# midi_block_R2_2.net
KiCad netlist of a schematic drawn in EAGLE
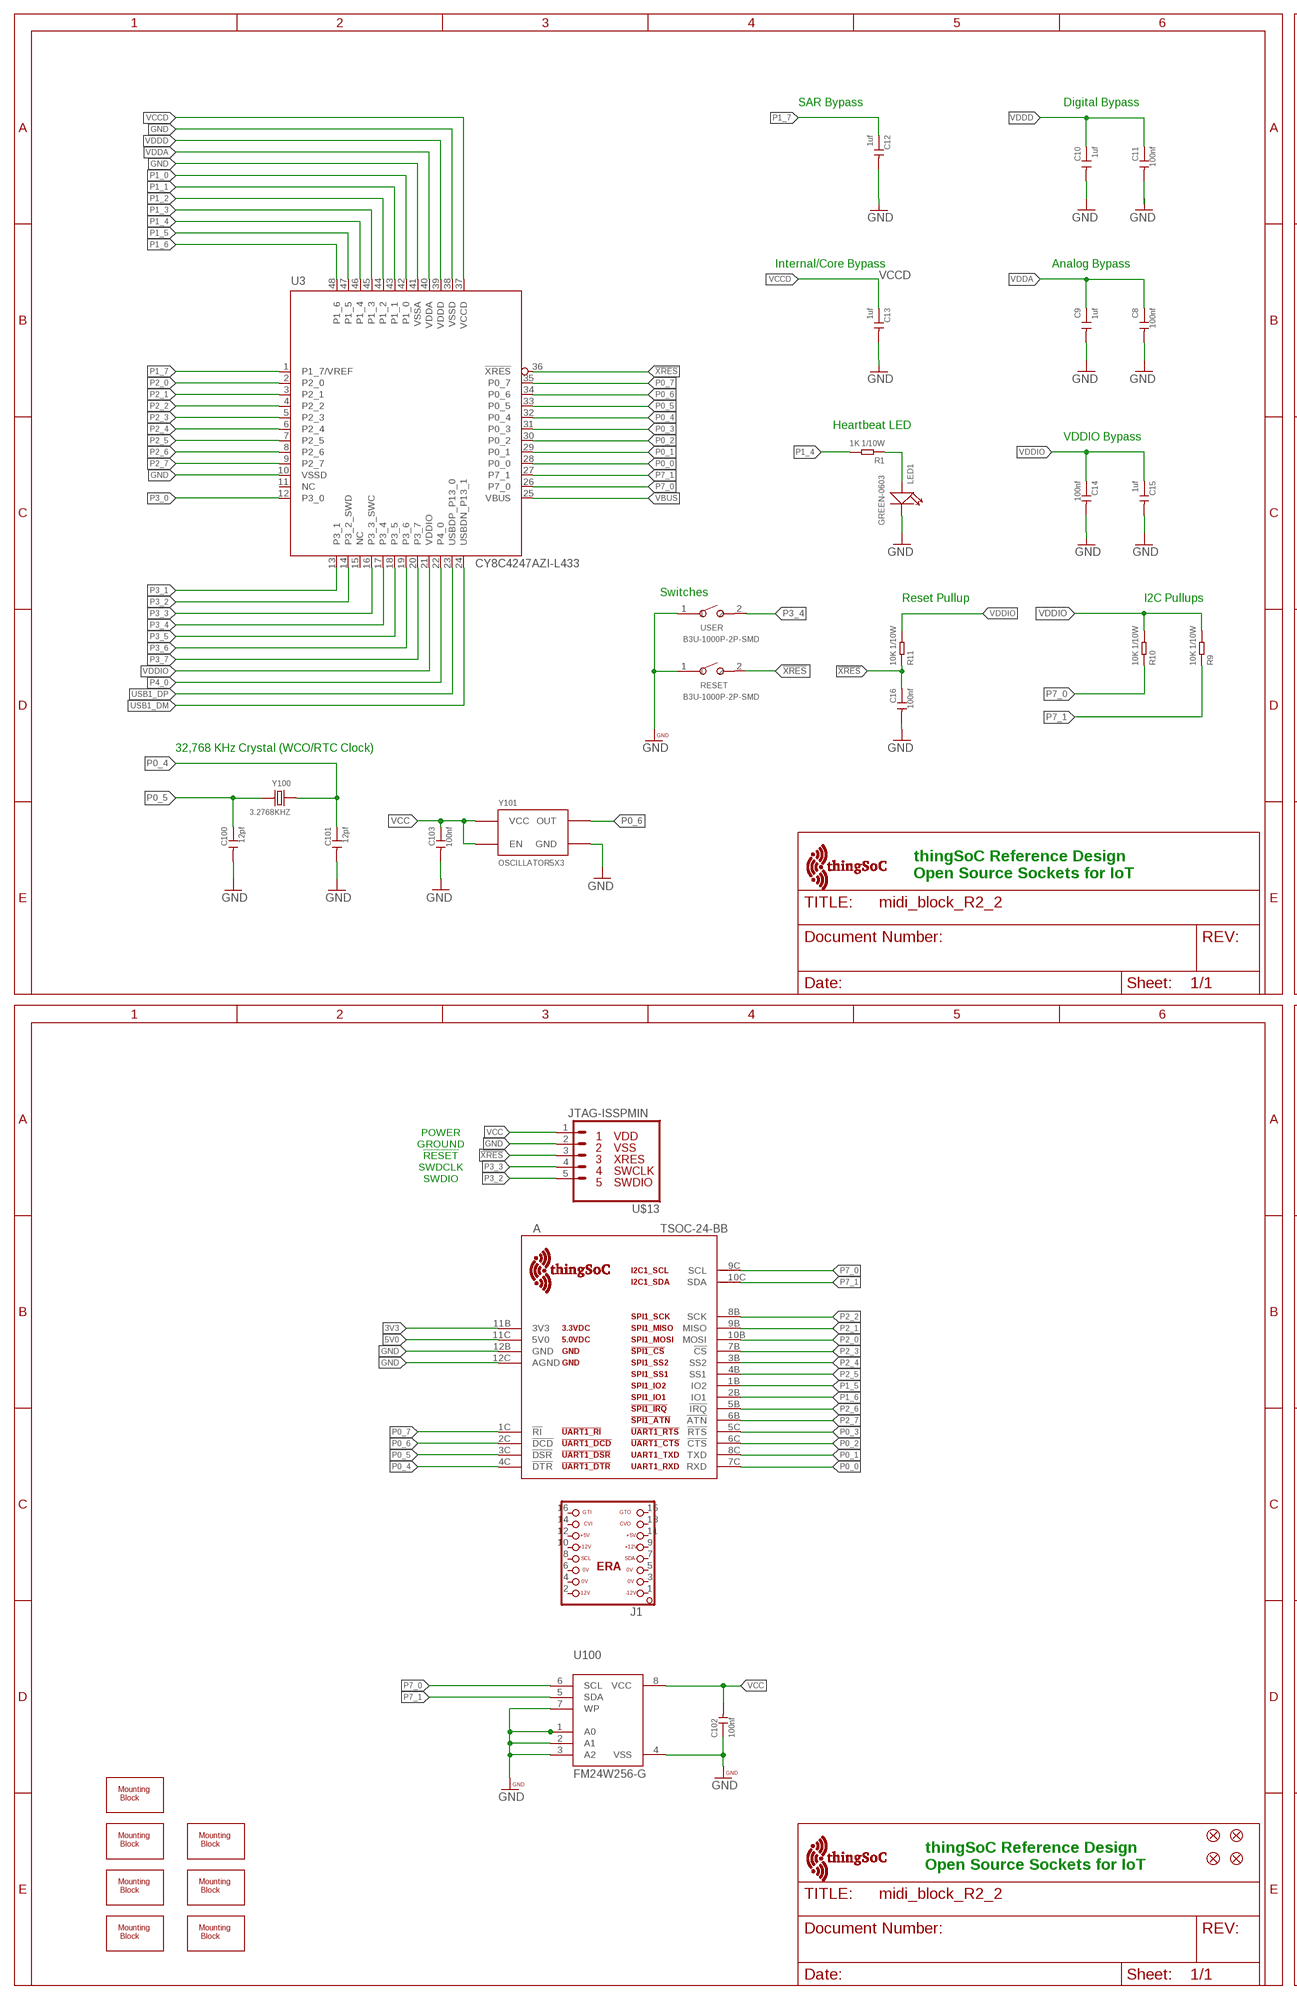
[diagram p0: schematic, sheet 1, part 1 of 2]
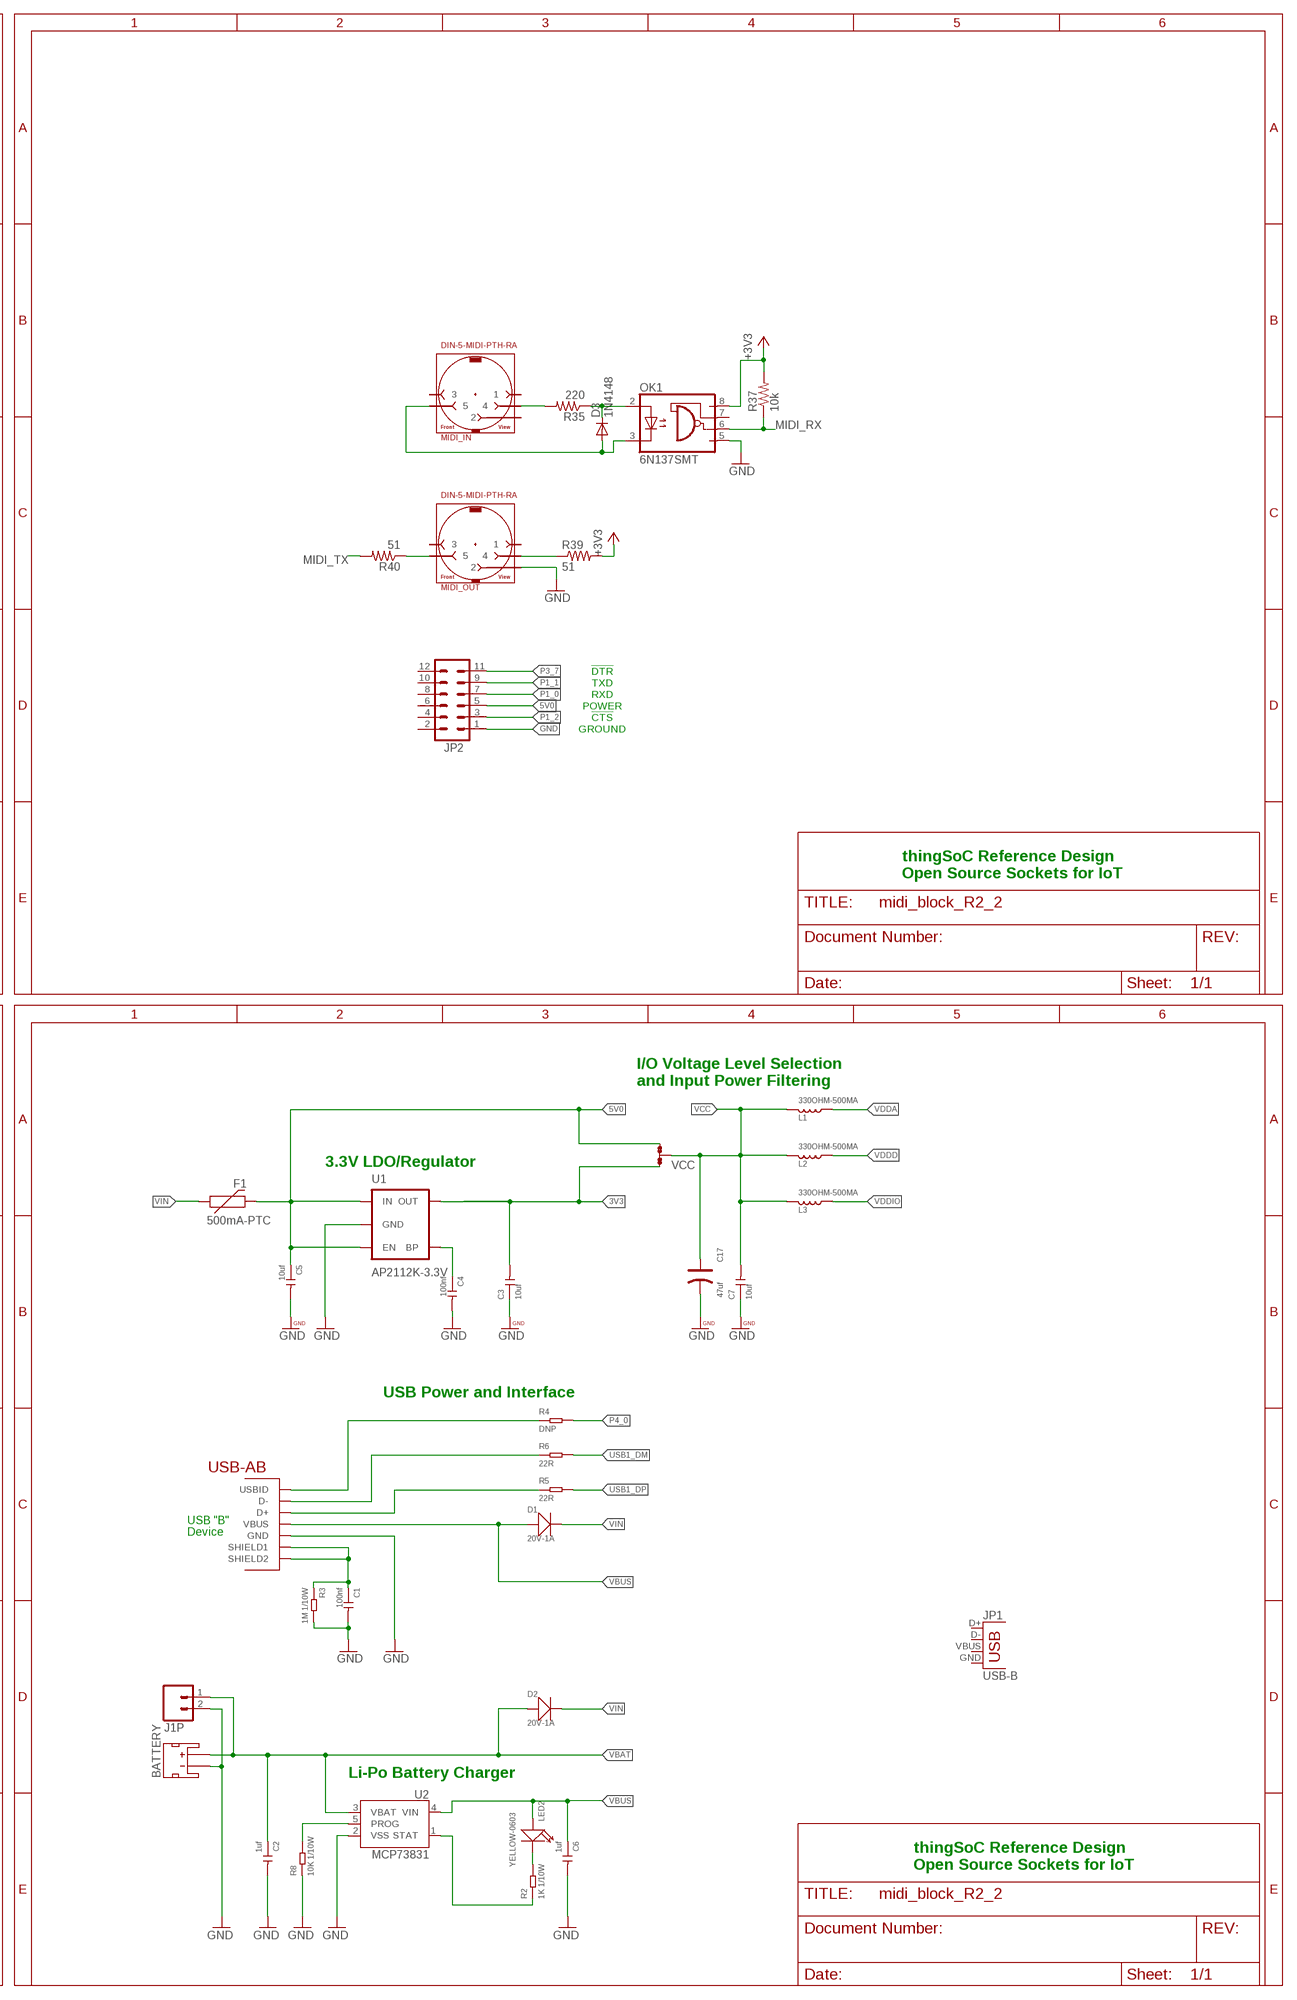
[diagram p1: schematic, sheet 1, part 2 of 2]

(export (version "E")
  (design (tool "Eeschema 10.0.6"))
  (components
    (comp (ref "A")
      (value "TSOC-24-BB")
      (footprint "eagle-import:TSOC-BB-S24")
      (libsource (lib "eagle-import") (part "TSOC-24-BB"))
    )
    (comp (ref "BATTERY")
      (value "JST_2MM_MALE")
      (footprint "eagle-import:JST-2-SMD")
      (libsource (lib "eagle-import") (part "JST_2MM_MALE"))
    )
    (comp (ref "C1")
      (value "100nf")
      (footprint "eagle-import:C0603")
      (fields (field (name "MPN") "CC0603KRX7R9BB104"))
      (libsource (lib "eagle-import") (part "CERAMIC-100NF-50V-10%-X7R(0603)"))
    )
    (comp (ref "C2")
      (value "1uf")
      (footprint "eagle-import:C0603")
      (fields (field (name "MPN") "CC0603KRX7R8BB105"))
      (libsource (lib "eagle-import") (part "CERAMIC-1UF-25V-10%-X7R(0603)"))
    )
    (comp (ref "C3")
      (value "10uf")
      (footprint "eagle-import:C0603")
      (fields (field (name "MPN") "CC0603KRX5R6BB106"))
      (libsource (lib "eagle-import") (part "CERAMIC-10UF-10V-10%-X5R(0603)"))
    )
    (comp (ref "C4")
      (value "100nf")
      (footprint "eagle-import:C0603")
      (fields (field (name "MPN") "CC0603KRX7R9BB104"))
      (libsource (lib "eagle-import") (part "CERAMIC-100NF-50V-10%-X7R(0603)"))
    )
    (comp (ref "C5")
      (value "10uf")
      (footprint "eagle-import:C0603")
      (fields (field (name "MPN") "CC0603KRX5R6BB106"))
      (libsource (lib "eagle-import") (part "CERAMIC-10UF-10V-10%-X5R(0603)"))
    )
    (comp (ref "C6")
      (value "1uf")
      (footprint "eagle-import:C0603")
      (fields (field (name "MPN") "CC0603KRX7R8BB105"))
      (libsource (lib "eagle-import") (part "CERAMIC-1UF-25V-10%-X7R(0603)"))
    )
    (comp (ref "C7")
      (value "10uf")
      (footprint "eagle-import:C0603")
      (fields (field (name "MPN") "CC0603KRX5R6BB106"))
      (libsource (lib "eagle-import") (part "CERAMIC-10UF-10V-10%-X5R(0603)"))
    )
    (comp (ref "C8")
      (value "100nf")
      (footprint "eagle-import:C0603")
      (fields (field (name "MPN") "CC0603KRX7R9BB104"))
      (libsource (lib "eagle-import") (part "CERAMIC-100NF-50V-10%-X7R(0603)"))
    )
    (comp (ref "C9")
      (value "1uf")
      (footprint "eagle-import:C0603")
      (fields (field (name "MPN") "CC0603KRX7R8BB105"))
      (libsource (lib "eagle-import") (part "CERAMIC-1UF-25V-10%-X7R(0603)"))
    )
    (comp (ref "C10")
      (value "1uf")
      (footprint "eagle-import:C0603")
      (fields (field (name "MPN") "CC0603KRX7R8BB105"))
      (libsource (lib "eagle-import") (part "CERAMIC-1UF-25V-10%-X7R(0603)"))
    )
    (comp (ref "C11")
      (value "100nf")
      (footprint "eagle-import:C0603")
      (fields (field (name "MPN") "CC0603KRX7R9BB104"))
      (libsource (lib "eagle-import") (part "CERAMIC-100NF-50V-10%-X7R(0603)"))
    )
    (comp (ref "C12")
      (value "1uf")
      (footprint "eagle-import:C0603")
      (fields (field (name "MPN") "CC0603KRX7R8BB105"))
      (libsource (lib "eagle-import") (part "CERAMIC-1UF-25V-10%-X7R(0603)"))
    )
    (comp (ref "C13")
      (value "1uf")
      (footprint "eagle-import:C0603")
      (fields (field (name "MPN") "CC0603KRX7R8BB105"))
      (libsource (lib "eagle-import") (part "CERAMIC-1UF-25V-10%-X7R(0603)"))
    )
    (comp (ref "C14")
      (value "100nf")
      (footprint "eagle-import:C0603")
      (fields (field (name "MPN") "CC0603KRX7R9BB104"))
      (libsource (lib "eagle-import") (part "CERAMIC-100NF-50V-10%-X7R(0603)"))
    )
    (comp (ref "C15")
      (value "1uf")
      (footprint "eagle-import:C0603")
      (fields (field (name "MPN") "CC0603KRX7R8BB105"))
      (libsource (lib "eagle-import") (part "CERAMIC-1UF-25V-10%-X7R(0603)"))
    )
    (comp (ref "C16")
      (value "100nf")
      (footprint "eagle-import:C0603")
      (fields (field (name "MPN") "CC0603KRX7R9BB104"))
      (libsource (lib "eagle-import") (part "CERAMIC-100NF-50V-10%-X7R(0603)"))
    )
    (comp (ref "C17")
      (value "47uf")
      (footprint "eagle-import:AVX-A")
      (fields (field (name "MPN") "TAJA476*006#NJ"))
      (libsource (lib "eagle-import") (part "TANTALUM-SMD-47UF-6.3V(AVX-A)"))
    )
    (comp (ref "C100")
      (value "12pf")
      (footprint "eagle-import:C0603")
      (fields (field (name "MPN") "CC0603JRNPO9BN120"))
      (libsource (lib "eagle-import") (part "CERAMIC-12PF-50V-5%-NPO(0603)"))
    )
    (comp (ref "C101")
      (value "12pf")
      (footprint "eagle-import:C0603")
      (fields (field (name "MPN") "CC0603JRNPO9BN120"))
      (libsource (lib "eagle-import") (part "CERAMIC-12PF-50V-5%-NPO(0603)"))
    )
    (comp (ref "C102")
      (value "100nf")
      (footprint "eagle-import:C0603")
      (fields (field (name "MPN") "CC0603KRX7R9BB104"))
      (libsource (lib "eagle-import") (part "CERAMIC-100NF-50V-10%-X7R(0603)"))
    )
    (comp (ref "C103")
      (value "100nf")
      (footprint "eagle-import:C0603")
      (fields (field (name "MPN") "CC0603KRX7R9BB104"))
      (libsource (lib "eagle-import") (part "CERAMIC-100NF-50V-10%-X7R(0603)"))
    )
    (comp (ref "D1")
      (value "20V-1A")
      (footprint "eagle-import:SOD-123")
      (fields (field (name "MPN") "B5819W"))
      (libsource (lib "eagle-import") (part "SMD-DIODE-SCHOTTKY-20V-1A(SOD-123)"))
    )
    (comp (ref "D2")
      (value "20V-1A")
      (footprint "eagle-import:SOD-123")
      (fields (field (name "MPN") "B5819W"))
      (libsource (lib "eagle-import") (part "SMD-DIODE-SCHOTTKY-20V-1A(SOD-123)"))
    )
    (comp (ref "D3")
      (value "1N4148")
      (footprint "eagle-import:SOD323-W")
      (libsource (lib "eagle-import") (part "DIODE-SOD323-W"))
    )
    (comp (ref "F1")
      (value "500mA-PTC")
      (footprint "eagle-import:PTC-1206")
      (libsource (lib "eagle-import") (part "PTCSMD"))
    )
    (comp (ref "FID1")
      (value "FIDUCIALUFIDUCIAL")
      (footprint "eagle-import:MICRO-FIDUCIAL")
      (libsource (lib "eagle-import") (part "FIDUCIALUFIDUCIAL"))
    )
    (comp (ref "FID2")
      (value "FIDUCIALUFIDUCIAL")
      (footprint "eagle-import:MICRO-FIDUCIAL")
      (libsource (lib "eagle-import") (part "FIDUCIALUFIDUCIAL"))
    )
    (comp (ref "FID3")
      (value "FIDUCIALUFIDUCIAL")
      (footprint "eagle-import:MICRO-FIDUCIAL")
      (libsource (lib "eagle-import") (part "FIDUCIALUFIDUCIAL"))
    )
    (comp (ref "FID4")
      (value "FIDUCIALUFIDUCIAL")
      (footprint "eagle-import:MICRO-FIDUCIAL")
      (libsource (lib "eagle-import") (part "FIDUCIALUFIDUCIAL"))
    )
    (comp (ref "J1")
      (value "ERA-SHROUD")
      (footprint "eagle-import:ERA")
      (libsource (lib "eagle-import") (part "ERA-SHROUD"))
    )
    (comp (ref "J1P")
      (value "M02-JST-2-PTH-NO_SILK")
      (footprint "eagle-import:JST-2-PTH-NS")
      (libsource (lib "eagle-import") (part "M02-JST-2-PTH-NO_SILK"))
    )
    (comp (ref "JP1")
      (value "USB-B")
      (footprint "eagle-import:USB-B-PTH")
      (libsource (lib "eagle-import") (part "USBPTH"))
    )
    (comp (ref "JP2")
      (value "M06X2FEMALE-SMT")
      (footprint "eagle-import:2X6_SMD")
      (libsource (lib "eagle-import") (part "M06X2FEMALE-SMT"))
    )
    (comp (ref "L1")
      (value "330OHM-500MA")
      (footprint "eagle-import:L0603")
      (fields (field (name "MPN") "BLM18AG121SN1D"))
      (libsource (lib "eagle-import") (part "SMD-FERRITE-CHIP-120-OHM-500MA(0603)"))
    )
    (comp (ref "L2")
      (value "330OHM-500MA")
      (footprint "eagle-import:L0603")
      (fields (field (name "MPN") "BLM18AG121SN1D"))
      (libsource (lib "eagle-import") (part "SMD-FERRITE-CHIP-120-OHM-500MA(0603)"))
    )
    (comp (ref "L3")
      (value "330OHM-500MA")
      (footprint "eagle-import:L0603")
      (fields (field (name "MPN") "BLM18AG121SN1D"))
      (libsource (lib "eagle-import") (part "SMD-FERRITE-CHIP-120-OHM-500MA(0603)"))
    )
    (comp (ref "LED1")
      (value "GREEN-0603")
      (footprint "eagle-import:LED-0603")
      (fields (field (name "MPN") "19-217-G7C-AN1P2-3T"))
      (libsource (lib "eagle-import") (part "SMD-LED-CLEAR-GREEN(0603)"))
    )
    (comp (ref "LED2")
      (value "YELLOW-0603")
      (footprint "eagle-import:LED-0603")
      (fields (field (name "MPN") "19-217-Y5C-AM1N1VY-3T"))
      (libsource (lib "eagle-import") (part "SMD-LED-CLEAR-YELLOW(0603)"))
    )
    (comp (ref "MIDI_IN")
      (value "DIN-5-MIDI-PTH-RA")
      (footprint "eagle-import:DIN-5-PTH-RA-SUPPORT")
      (libsource (lib "eagle-import") (part "DIN-5-MIDI-PTH-RA"))
    )
    (comp (ref "MIDI_OUT")
      (value "DIN-5-MIDI-PTH-RA")
      (footprint "eagle-import:DIN-5-PTH-RA-SUPPORT")
      (libsource (lib "eagle-import") (part "DIN-5-MIDI-PTH-RA"))
    )
    (comp (ref "OK1")
      (value "6N137SMT")
      (footprint "eagle-import:DIL8-SMD")
      (libsource (lib "eagle-import") (part "6N137SMT"))
    )
    (comp (ref "R1")
      (value "1K 1/10W")
      (footprint "eagle-import:R0603")
      (fields (field (name "MPN") "RC0603JR-071KL"))
      (libsource (lib "eagle-import") (part "SMD-RES-1K-5%-1/10W(0603)"))
    )
    (comp (ref "R2")
      (value "1K 1/10W")
      (footprint "eagle-import:R0603")
      (fields (field (name "MPN") "RC0603JR-071KL"))
      (libsource (lib "eagle-import") (part "SMD-RES-1K-5%-1/10W(0603)"))
    )
    (comp (ref "R3")
      (value "1M 1/10W")
      (footprint "eagle-import:R0603")
      (fields (field (name "MPN") "RC0603JR-071ML"))
      (libsource (lib "eagle-import") (part "SMD-RES-1M-5%-1/10W(0603)"))
    )
    (comp (ref "R4")
      (value "DNP")
      (footprint "eagle-import:R0603")
      (fields (field (name "MPN") "RC0603JR-0722RL"))
      (libsource (lib "eagle-import") (part "SMD-RES-22R-5%-1/10W(0603)"))
    )
    (comp (ref "R5")
      (value "22R")
      (footprint "eagle-import:R0603")
      (fields (field (name "MPN") "RC0603JR-0722RL"))
      (libsource (lib "eagle-import") (part "SMD-RES-22R-5%-1/10W(0603)"))
    )
    (comp (ref "R6")
      (value "22R")
      (footprint "eagle-import:R0603")
      (fields (field (name "MPN") "RC0603JR-0722RL"))
      (libsource (lib "eagle-import") (part "SMD-RES-22R-5%-1/10W(0603)"))
    )
    (comp (ref "R8")
      (value "10K 1/10W")
      (footprint "eagle-import:R0603")
      (fields (field (name "MPN") "RC0603JR-0710KL"))
      (libsource (lib "eagle-import") (part "SMD-RES-10K-5%-1/10W(0603)"))
    )
    (comp (ref "R9")
      (value "10K 1/10W")
      (footprint "eagle-import:R0603")
      (fields (field (name "MPN") "RC0603JR-0710KL"))
      (libsource (lib "eagle-import") (part "SMD-RES-10K-5%-1/10W(0603)"))
    )
    (comp (ref "R10")
      (value "10K 1/10W")
      (footprint "eagle-import:R0603")
      (fields (field (name "MPN") "RC0603JR-0710KL"))
      (libsource (lib "eagle-import") (part "SMD-RES-10K-5%-1/10W(0603)"))
    )
    (comp (ref "R11")
      (value "10K 1/10W")
      (footprint "eagle-import:R0603")
      (fields (field (name "MPN") "RC0603JR-0710KL"))
      (libsource (lib "eagle-import") (part "SMD-RES-10K-5%-1/10W(0603)"))
    )
    (comp (ref "R35")
      (value "220")
      (footprint "eagle-import:R0603")
      (libsource (lib "eagle-import") (part "R-US_R0603"))
    )
    (comp (ref "R37")
      (value "10k")
      (footprint "eagle-import:R0603")
      (libsource (lib "eagle-import") (part "R-US_R0603"))
    )
    (comp (ref "R39")
      (value "51")
      (footprint "eagle-import:R0603")
      (libsource (lib "eagle-import") (part "R-US_R0603"))
    )
    (comp (ref "R40")
      (value "51")
      (footprint "eagle-import:R0603")
      (libsource (lib "eagle-import") (part "R-US_R0603"))
    )
    (comp (ref "RESET")
      (value "B3U-1000P-2P-SMD")
      (footprint "eagle-import:SW2-2.6-3.0X2.5X1.2+0.4MM")
      (libsource (lib "eagle-import") (part "SMD-BUTTON(2P-3.0X2.5X1.2+0.4MM)-B3U-1000P-2P-SMD"))
    )
    (comp (ref "U$1")
      (value "PCB-MB-SIDE")
      (footprint "eagle-import:PCB-MB-01-SIDE")
      (libsource (lib "eagle-import") (part "PCB-MB-SIDE"))
    )
    (comp (ref "U$7")
      (value "PCB-MB-SIDE")
      (footprint "eagle-import:PCB-MB-01-SIDE")
      (libsource (lib "eagle-import") (part "PCB-MB-SIDE"))
    )
    (comp (ref "U$8")
      (value "PCB-MB-SIDE")
      (footprint "eagle-import:PCB-MB-01-SIDE")
      (libsource (lib "eagle-import") (part "PCB-MB-SIDE"))
    )
    (comp (ref "U$9")
      (value "PCB-MB-SIDE")
      (footprint "eagle-import:PCB-MB-01-SIDE")
      (libsource (lib "eagle-import") (part "PCB-MB-SIDE"))
    )
    (comp (ref "U$10")
      (value "PCB-MB-SIDE")
      (footprint "eagle-import:PCB-MB-01-SIDE")
      (libsource (lib "eagle-import") (part "PCB-MB-SIDE"))
    )
    (comp (ref "U$11")
      (value "PCB-MB-SIDE")
      (footprint "eagle-import:PCB-MB-01-SIDE")
      (libsource (lib "eagle-import") (part "PCB-MB-SIDE"))
    )
    (comp (ref "U$12")
      (value "PCB-MB-SIDE")
      (footprint "eagle-import:PCB-MB-01-SIDE")
      (libsource (lib "eagle-import") (part "PCB-MB-SIDE"))
    )
    (comp (ref "U$13")
      (value "JTAG-ISSPMIN")
      (footprint "eagle-import:PSOC_JTAG_MINSILK")
      (libsource (lib "eagle-import") (part "JTAG-ISSPMIN"))
    )
    (comp (ref "U$100")
      (value "TSOC-LOGO-LRG")
      (footprint "eagle-import:TSOC-LOGO-LRG")
      (libsource (lib "eagle-import") (part "TSOC-LOGO-LRG"))
    )
    (comp (ref "U$101")
      (value "TSOC-LOGO-SMALL")
      (footprint "eagle-import:TSOC-LOGO-SML")
      (libsource (lib "eagle-import") (part "TSOC-LOGO-SMALL"))
    )
    (comp (ref "U1")
      (value "AP2112K-3.3V")
      (footprint "eagle-import:SOT23-5")
      (libsource (lib "eagle-import") (part "V_REG_LDOSMD"))
    )
    (comp (ref "U2")
      (value "MCP73831")
      (footprint "eagle-import:SOT23-5")
      (libsource (lib "eagle-import") (part "MCP73831"))
    )
    (comp (ref "U3")
      (value "CY8C4247AZI-L433")
      (footprint "eagle-import:TQFP-7X7-48")
      (libsource (lib "eagle-import") (part "CY8C4247AZI-L433"))
    )
    (comp (ref "U100")
      (value "FM24W256-G")
      (footprint "eagle-import:SO08")
      (libsource (lib "eagle-import") (part "FM24W256-G"))
    )
    (comp (ref "USB")
      (value "USB_AB")
      (footprint "eagle-import:USB-AB-MICRO-SMD")
      (libsource (lib "eagle-import") (part "USB_AB"))
    )
    (comp (ref "USER")
      (value "B3U-1000P-2P-SMD")
      (footprint "eagle-import:SW2-2.6-3.0X2.5X1.2+0.4MM")
      (libsource (lib "eagle-import") (part "SMD-BUTTON(2P-3.0X2.5X1.2+0.4MM)-B3U-1000P-2P-SMD"))
    )
    (comp (ref "VCC")
      (value "JMP-3-1_2")
      (footprint "eagle-import:JMP-3-1_2")
      (libsource (lib "eagle-import") (part "JMP-3-1_2"))
    )
    (comp (ref "Y100")
      (value "3.2768KHZ")
      (footprint "eagle-import:X2-SMD-L2.0X1.2X0.55MM")
      (fields (field (name "MPN") "FC-12M"))
      (libsource (lib "eagle-import") (part "SMD-CRYSTAL-32.768KHZ-12.5PF-20PPM-90K(2P-L2.0X1.2MM)"))
    )
    (comp (ref "Y101")
      (value "OSCILLATOR5X3")
      (footprint "eagle-import:CRYSTAL-SMD-5X3")
      (libsource (lib "eagle-import") (part "OSCILLATOR5X3"))
    )
  )
  (nets
    (net (code "1") (name "+3V3") (class "Default")
      (node (ref "OK1") (pin "8") (pinfunction "VCC_8") (pintype "passive"))
      (node (ref "R37") (pin "2") (pinfunction "2_2") (pintype "passive"))
      (node (ref "R39") (pin "2") (pinfunction "2_2") (pintype "passive"))
    )
    (net (code "2") (name "/MIDI_RX") (class "Default")
      (node (ref "OK1") (pin "6") (pinfunction "VO_6") (pintype "passive"))
      (node (ref "R37") (pin "1") (pinfunction "1_1") (pintype "passive"))
    )
    (net (code "3") (name "/MIDI_TX") (class "Default")
      (node (ref "R40") (pin "2") (pinfunction "2_2") (pintype "passive"))
    )
    (net (code "4") (name "/~{XRES}") (class "Default")
      (node (ref "C16") (pin "1") (pinfunction "1_1") (pintype "passive"))
      (node (ref "R11") (pin "1") (pinfunction "1_1") (pintype "passive"))
      (node (ref "RESET") (pin "2") (pinfunction "2_2") (pintype "bidirectional"))
      (node (ref "U$13") (pin "3") (pinfunction "3_3") (pintype "passive"))
      (node (ref "U3") (pin "36") (pinfunction "~{XRES}_36") (pintype "bidirectional"))
    )
    (net (code "5") (name "3V3") (class "Default")
      (node (ref "A") (pin "11B") (pinfunction "3V3_11B") (pintype "bidirectional"))
      (node (ref "C3") (pin "2") (pinfunction "2_2") (pintype "passive"))
      (node (ref "U1") (pin "5") (pinfunction "OUT_5") (pintype "passive"))
      (node (ref "VCC") (pin "1") (pinfunction "1_1") (pintype "passive"))
    )
    (net (code "6") (name "5V0") (class "Default")
      (node (ref "A") (pin "11C") (pinfunction "5V0_11C") (pintype "bidirectional"))
      (node (ref "C5") (pin "1") (pinfunction "1_1") (pintype "passive"))
      (node (ref "F1") (pin "2") (pinfunction "2_2") (pintype "bidirectional"))
      (node (ref "JP2") (pin "5") (pinfunction "5_5") (pintype "passive"))
      (node (ref "U1") (pin "1") (pinfunction "IN_1") (pintype "input"))
      (node (ref "U1") (pin "3") (pinfunction "EN_3") (pintype "input"))
      (node (ref "VCC") (pin "3") (pinfunction "3_3") (pintype "passive"))
    )
    (net (code "7") (name "GND") (class "Default")
      (node (ref "A") (pin "12B") (pinfunction "GND_12B") (pintype "bidirectional"))
      (node (ref "A") (pin "12C") (pinfunction "AGND_12C") (pintype "bidirectional"))
      (node (ref "BATTERY") (pin "1") (pinfunction "-_1") (pintype "bidirectional"))
      (node (ref "C1") (pin "2") (pinfunction "2_2") (pintype "passive"))
      (node (ref "C10") (pin "2") (pinfunction "2_2") (pintype "passive"))
      (node (ref "C100") (pin "2") (pinfunction "2_2") (pintype "passive"))
      (node (ref "C101") (pin "2") (pinfunction "2_2") (pintype "passive"))
      (node (ref "C102") (pin "1") (pinfunction "1_1") (pintype "passive"))
      (node (ref "C103") (pin "2") (pinfunction "2_2") (pintype "passive"))
      (node (ref "C11") (pin "2") (pinfunction "2_2") (pintype "passive"))
      (node (ref "C12") (pin "2") (pinfunction "2_2") (pintype "passive"))
      (node (ref "C13") (pin "2") (pinfunction "2_2") (pintype "passive"))
      (node (ref "C14") (pin "2") (pinfunction "2_2") (pintype "passive"))
      (node (ref "C15") (pin "2") (pinfunction "2_2") (pintype "passive"))
      (node (ref "C16") (pin "2") (pinfunction "2_2") (pintype "passive"))
      (node (ref "C17") (pin "-") (pinfunction "-_-") (pintype "passive"))
      (node (ref "C2") (pin "2") (pinfunction "2_2") (pintype "passive"))
      (node (ref "C3") (pin "1") (pinfunction "1_1") (pintype "passive"))
      (node (ref "C4") (pin "2") (pinfunction "2_2") (pintype "passive"))
      (node (ref "C5") (pin "2") (pinfunction "2_2") (pintype "passive"))
      (node (ref "C6") (pin "2") (pinfunction "2_2") (pintype "passive"))
      (node (ref "C7") (pin "1") (pinfunction "1_1") (pintype "passive"))
      (node (ref "C8") (pin "2") (pinfunction "2_2") (pintype "passive"))
      (node (ref "C9") (pin "2") (pinfunction "2_2") (pintype "passive"))
      (node (ref "J1P") (pin "2") (pinfunction "2_2") (pintype "passive"))
      (node (ref "JP2") (pin "1") (pinfunction "1_1") (pintype "passive"))
      (node (ref "LED1") (pin "-") (pinfunction "-_-") (pintype "passive"))
      (node (ref "MIDI_OUT") (pin "2") (pinfunction "2_2") (pintype "bidirectional"))
      (node (ref "OK1") (pin "5") (pinfunction "GND_5") (pintype "passive"))
      (node (ref "R3") (pin "2") (pinfunction "2_2") (pintype "passive"))
      (node (ref "R8") (pin "1") (pinfunction "1_1") (pintype "passive"))
      (node (ref "RESET") (pin "1") (pinfunction "1_1") (pintype "bidirectional"))
      (node (ref "U$13") (pin "2") (pinfunction "2_2") (pintype "passive"))
      (node (ref "U1") (pin "2") (pinfunction "GND_2") (pintype "input"))
      (node (ref "U100") (pin "1") (pinfunction "A0_1") (pintype "bidirectional"))
      (node (ref "U100") (pin "2") (pinfunction "A1_2") (pintype "bidirectional"))
      (node (ref "U100") (pin "3") (pinfunction "A2_3") (pintype "bidirectional"))
      (node (ref "U100") (pin "4") (pinfunction "VSS_4") (pintype "power_in"))
      (node (ref "U100") (pin "7") (pinfunction "WP_7") (pintype "bidirectional"))
      (node (ref "U2") (pin "2") (pinfunction "VSS_2") (pintype "power_in"))
      (node (ref "U3") (pin "10") (pinfunction "VSSD_10") (pintype "bidirectional"))
      (node (ref "U3") (pin "38") (pinfunction "VSSD_38") (pintype "bidirectional"))
      (node (ref "U3") (pin "41") (pinfunction "VSSA_41") (pintype "bidirectional"))
      (node (ref "USB") (pin "GND") (pinfunction "GND_GND") (pintype "bidirectional"))
      (node (ref "USER") (pin "1") (pinfunction "1_1") (pintype "bidirectional"))
      (node (ref "Y101") (pin "2") (pinfunction "GND_2") (pintype "bidirectional"))
    )
    (net (code "8") (name "Net-(C1-Pad1)") (class "Default")
      (node (ref "C1") (pin "1") (pinfunction "1_1") (pintype "passive"))
      (node (ref "R3") (pin "1") (pinfunction "1_1") (pintype "passive"))
      (node (ref "USB") (pin "SHIELD1") (pinfunction "SHIELD1_SHIELD1") (pintype "bidirectional"))
      (node (ref "USB") (pin "SHIELD2") (pinfunction "SHIELD2_SHIELD2") (pintype "bidirectional"))
    )
    (net (code "9") (name "Net-(LED1-Pad+)") (class "Default")
      (node (ref "LED1") (pin "+") (pinfunction "+_+") (pintype "passive"))
      (node (ref "R1") (pin "1") (pinfunction "1_1") (pintype "passive"))
    )
    (net (code "10") (name "Net-(LED2-Pad-)") (class "Default")
      (node (ref "LED2") (pin "-") (pinfunction "-_-") (pintype "passive"))
      (node (ref "R2") (pin "2") (pinfunction "2_2") (pintype "passive"))
    )
    (net (code "11") (name "Net-(MIDI_IN-Pad4)") (class "Default")
      (node (ref "MIDI_IN") (pin "4") (pinfunction "4_4") (pintype "bidirectional"))
      (node (ref "R35") (pin "2") (pinfunction "2_2") (pintype "passive"))
    )
    (net (code "12") (name "Net-(MIDI_OUT-Pad4)") (class "Default")
      (node (ref "MIDI_OUT") (pin "4") (pinfunction "4_4") (pintype "bidirectional"))
      (node (ref "R39") (pin "1") (pinfunction "1_1") (pintype "passive"))
    )
    (net (code "13") (name "Net-(MIDI_OUT-Pad5)") (class "Default")
      (node (ref "MIDI_OUT") (pin "5") (pinfunction "5_5") (pintype "bidirectional"))
      (node (ref "R40") (pin "1") (pinfunction "1_1") (pintype "passive"))
    )
    (net (code "14") (name "Net-(OK1-A)") (class "Default")
      (node (ref "D3") (pin "C") (pinfunction "C_C") (pintype "passive"))
      (node (ref "OK1") (pin "2") (pinfunction "A_2") (pintype "passive"))
      (node (ref "R35") (pin "1") (pinfunction "1_1") (pintype "passive"))
    )
    (net (code "15") (name "Net-(OK1-C)") (class "Default")
      (node (ref "D3") (pin "A") (pinfunction "A_A") (pintype "passive"))
      (node (ref "MIDI_IN") (pin "5") (pinfunction "5_5") (pintype "bidirectional"))
      (node (ref "OK1") (pin "3") (pinfunction "C_3") (pintype "passive"))
    )
    (net (code "16") (name "Net-(R5-Pad1)") (class "Default")
      (node (ref "R5") (pin "1") (pinfunction "1_1") (pintype "passive"))
      (node (ref "USB") (pin "D+") (pinfunction "D+_D+") (pintype "bidirectional"))
    )
    (net (code "17") (name "Net-(R6-Pad1)") (class "Default")
      (node (ref "R6") (pin "1") (pinfunction "1_1") (pintype "passive"))
      (node (ref "USB") (pin "D-") (pinfunction "D-_D-") (pintype "bidirectional"))
    )
    (net (code "18") (name "Net-(U1-BP)") (class "Default")
      (node (ref "C4") (pin "1") (pinfunction "1_1") (pintype "passive"))
      (node (ref "U1") (pin "4") (pinfunction "BP_4") (pintype "input"))
    )
    (net (code "19") (name "Net-(U2-PROG)") (class "Default")
      (node (ref "R8") (pin "2") (pinfunction "2_2") (pintype "passive"))
      (node (ref "U2") (pin "5") (pinfunction "PROG_5") (pintype "input"))
    )
    (net (code "20") (name "Net-(U2-STAT)") (class "Default")
      (node (ref "R2") (pin "1") (pinfunction "1_1") (pintype "passive"))
      (node (ref "U2") (pin "1") (pinfunction "STAT_1") (pintype "output"))
    )
    (net (code "21") (name "Net-(USB-USBID)") (class "Default")
      (node (ref "R4") (pin "1") (pinfunction "1_1") (pintype "passive"))
      (node (ref "USB") (pin "ID") (pinfunction "USBID_ID") (pintype "bidirectional"))
    )
    (net (code "22") (name "P0_0") (class "Default")
      (node (ref "A") (pin "7C") (pinfunction "RXD_7C") (pintype "bidirectional"))
      (node (ref "U3") (pin "28") (pinfunction "P0_0_28") (pintype "bidirectional"))
    )
    (net (code "23") (name "P0_1") (class "Default")
      (node (ref "A") (pin "8C") (pinfunction "TXD_8C") (pintype "bidirectional"))
      (node (ref "U3") (pin "29") (pinfunction "P0_1_29") (pintype "bidirectional"))
    )
    (net (code "24") (name "P0_2") (class "Default")
      (node (ref "A") (pin "6C") (pinfunction "~{CTS}_6C") (pintype "bidirectional"))
      (node (ref "U3") (pin "30") (pinfunction "P0_2_30") (pintype "input"))
    )
    (net (code "25") (name "P0_3") (class "Default")
      (node (ref "A") (pin "5C") (pinfunction "~{RTS}_5C") (pintype "bidirectional"))
      (node (ref "U3") (pin "31") (pinfunction "P0_3_31") (pintype "bidirectional"))
    )
    (net (code "26") (name "P0_4") (class "Default")
      (node (ref "A") (pin "4C") (pinfunction "~{DTR}_4C") (pintype "bidirectional"))
      (node (ref "C101") (pin "1") (pinfunction "1_1") (pintype "passive"))
      (node (ref "U3") (pin "32") (pinfunction "P0_4_32") (pintype "bidirectional"))
      (node (ref "Y100") (pin "1") (pinfunction "1_1") (pintype "passive"))
    )
    (net (code "27") (name "P0_5") (class "Default")
      (node (ref "A") (pin "3C") (pinfunction "~{DSR}_3C") (pintype "bidirectional"))
      (node (ref "C100") (pin "1") (pinfunction "1_1") (pintype "passive"))
      (node (ref "U3") (pin "33") (pinfunction "P0_5_33") (pintype "bidirectional"))
      (node (ref "Y100") (pin "2") (pinfunction "2_2") (pintype "passive"))
    )
    (net (code "28") (name "P0_6") (class "Default")
      (node (ref "A") (pin "2C") (pinfunction "~{DCD}_2C") (pintype "bidirectional"))
      (node (ref "U3") (pin "34") (pinfunction "P0_6_34") (pintype "power_in"))
      (node (ref "Y101") (pin "3") (pinfunction "OUT_3") (pintype "bidirectional"))
    )
    (net (code "29") (name "P0_7") (class "Default")
      (node (ref "A") (pin "1C") (pinfunction "~{RI}_1C") (pintype "bidirectional"))
      (node (ref "U3") (pin "35") (pinfunction "P0_7_35") (pintype "bidirectional"))
    )
    (net (code "30") (name "P1_0") (class "Default")
      (node (ref "JP2") (pin "7") (pinfunction "7_7") (pintype "passive"))
      (node (ref "U3") (pin "42") (pinfunction "P1_0_42") (pintype "bidirectional"))
    )
    (net (code "31") (name "P1_1") (class "Default")
      (node (ref "JP2") (pin "9") (pinfunction "9_9") (pintype "passive"))
      (node (ref "U3") (pin "43") (pinfunction "P1_1_43") (pintype "bidirectional"))
    )
    (net (code "32") (name "P1_2") (class "Default")
      (node (ref "JP2") (pin "3") (pinfunction "3_3") (pintype "passive"))
      (node (ref "U3") (pin "44") (pinfunction "P1_2_44") (pintype "power_in"))
    )
    (net (code "33") (name "P1_3") (class "Default")
      (node (ref "U3") (pin "45") (pinfunction "P1_3_45") (pintype "bidirectional"))
    )
    (net (code "34") (name "P1_4") (class "Default")
      (node (ref "R1") (pin "2") (pinfunction "2_2") (pintype "passive"))
      (node (ref "U3") (pin "46") (pinfunction "P1_4_46") (pintype "bidirectional"))
    )
    (net (code "35") (name "P1_5") (class "Default")
      (node (ref "A") (pin "1B") (pinfunction "IO2_1B") (pintype "bidirectional"))
      (node (ref "U3") (pin "47") (pinfunction "P1_5_47") (pintype "bidirectional"))
    )
    (net (code "36") (name "P1_6") (class "Default")
      (node (ref "A") (pin "2B") (pinfunction "IO1_2B") (pintype "bidirectional"))
      (node (ref "U3") (pin "48") (pinfunction "P1_6_48") (pintype "bidirectional"))
    )
    (net (code "37") (name "P1_7") (class "Default")
      (node (ref "C12") (pin "1") (pinfunction "1_1") (pintype "passive"))
      (node (ref "U3") (pin "1") (pinfunction "P1_7/VREF_1") (pintype "bidirectional"))
    )
    (net (code "38") (name "P2_0") (class "Default")
      (node (ref "A") (pin "10B") (pinfunction "MOSI_10B") (pintype "bidirectional"))
      (node (ref "U3") (pin "2") (pinfunction "P2_0_2") (pintype "bidirectional"))
    )
    (net (code "39") (name "P2_1") (class "Default")
      (node (ref "A") (pin "9B") (pinfunction "MISO_9B") (pintype "bidirectional"))
      (node (ref "U3") (pin "3") (pinfunction "P2_1_3") (pintype "bidirectional"))
    )
    (net (code "40") (name "P2_2") (class "Default")
      (node (ref "A") (pin "8B") (pinfunction "SCK_8B") (pintype "bidirectional"))
      (node (ref "U3") (pin "4") (pinfunction "P2_2_4") (pintype "power_in"))
    )
    (net (code "41") (name "P2_3") (class "Default")
      (node (ref "A") (pin "7B") (pinfunction "~{CS}_7B") (pintype "bidirectional"))
      (node (ref "U3") (pin "5") (pinfunction "P2_3_5") (pintype "bidirectional"))
    )
    (net (code "42") (name "P2_4") (class "Default")
      (node (ref "A") (pin "3B") (pinfunction "SS2_3B") (pintype "bidirectional"))
      (node (ref "U3") (pin "6") (pinfunction "P2_4_6") (pintype "bidirectional"))
    )
    (net (code "43") (name "P2_5") (class "Default")
      (node (ref "A") (pin "4B") (pinfunction "SS1_4B") (pintype "bidirectional"))
      (node (ref "U3") (pin "7") (pinfunction "P2_5_7") (pintype "bidirectional"))
    )
    (net (code "44") (name "P2_6") (class "Default")
      (node (ref "A") (pin "5B") (pinfunction "~{IRQ}_5B") (pintype "bidirectional"))
      (node (ref "U3") (pin "8") (pinfunction "P2_6_8") (pintype "power_in"))
    )
    (net (code "45") (name "P2_7") (class "Default")
      (node (ref "A") (pin "6B") (pinfunction "~{ATN}_6B") (pintype "bidirectional"))
      (node (ref "U3") (pin "9") (pinfunction "P2_7_9") (pintype "bidirectional"))
    )
    (net (code "46") (name "P3_0") (class "Default")
      (node (ref "U3") (pin "12") (pinfunction "P3_0_12") (pintype "bidirectional"))
    )
    (net (code "47") (name "P3_1") (class "Default")
      (node (ref "U3") (pin "13") (pinfunction "P3_1_13") (pintype "bidirectional"))
    )
    (net (code "48") (name "P3_2") (class "Default")
      (node (ref "U$13") (pin "5") (pinfunction "5_5") (pintype "passive"))
      (node (ref "U3") (pin "14") (pinfunction "P3_2_SWD_14") (pintype "bidirectional"))
    )
    (net (code "49") (name "P3_3") (class "Default")
      (node (ref "U$13") (pin "4") (pinfunction "4_4") (pintype "passive"))
      (node (ref "U3") (pin "16") (pinfunction "P3_3_SWC_16") (pintype "bidirectional"))
    )
    (net (code "50") (name "P3_4") (class "Default")
      (node (ref "U3") (pin "17") (pinfunction "P3_4_17") (pintype "bidirectional"))
      (node (ref "USER") (pin "2") (pinfunction "2_2") (pintype "bidirectional"))
    )
    (net (code "51") (name "P3_5") (class "Default")
      (node (ref "U3") (pin "18") (pinfunction "P3_5_18") (pintype "bidirectional"))
    )
    (net (code "52") (name "P3_6") (class "Default")
      (node (ref "U3") (pin "19") (pinfunction "P3_6_19") (pintype "power_in"))
    )
    (net (code "53") (name "P3_7") (class "Default")
      (node (ref "JP2") (pin "11") (pinfunction "11_11") (pintype "passive"))
      (node (ref "U3") (pin "20") (pinfunction "P3_7_20") (pintype "bidirectional"))
    )
    (net (code "54") (name "P4_0") (class "Default")
      (node (ref "R4") (pin "2") (pinfunction "2_2") (pintype "passive"))
      (node (ref "U3") (pin "22") (pinfunction "P4_0_22") (pintype "bidirectional"))
    )
    (net (code "55") (name "P7_0") (class "Default")
      (node (ref "A") (pin "9C") (pinfunction "SCL_9C") (pintype "bidirectional"))
      (node (ref "R10") (pin "1") (pinfunction "1_1") (pintype "passive"))
      (node (ref "U100") (pin "6") (pinfunction "SCL_6") (pintype "bidirectional"))
      (node (ref "U3") (pin "26") (pinfunction "P7_0_26") (pintype "bidirectional"))
    )
    (net (code "56") (name "P7_1") (class "Default")
      (node (ref "A") (pin "10C") (pinfunction "SDA_10C") (pintype "bidirectional"))
      (node (ref "R9") (pin "1") (pinfunction "1_1") (pintype "passive"))
      (node (ref "U100") (pin "5") (pinfunction "SDA_5") (pintype "bidirectional"))
      (node (ref "U3") (pin "27") (pinfunction "P7_1_27") (pintype "bidirectional"))
    )
    (net (code "57") (name "USB1_DM") (class "Default")
      (node (ref "R6") (pin "2") (pinfunction "2_2") (pintype "passive"))
      (node (ref "U3") (pin "24") (pinfunction "USBDN_P13_1_24") (pintype "bidirectional"))
    )
    (net (code "58") (name "USB1_DP") (class "Default")
      (node (ref "R5") (pin "2") (pinfunction "2_2") (pintype "passive"))
      (node (ref "U3") (pin "23") (pinfunction "USBDP_P13_0_23") (pintype "bidirectional"))
    )
    (net (code "59") (name "VBAT") (class "Default")
      (node (ref "BATTERY") (pin "2") (pinfunction "+_2") (pintype "bidirectional"))
      (node (ref "C2") (pin "1") (pinfunction "1_1") (pintype "passive"))
      (node (ref "D2") (pin "+") (pinfunction "+_+") (pintype "passive"))
      (node (ref "J1P") (pin "1") (pinfunction "1_1") (pintype "passive"))
      (node (ref "U2") (pin "3") (pinfunction "VBAT_3") (pintype "power_in"))
    )
    (net (code "60") (name "VBUS") (class "Default")
      (node (ref "C6") (pin "1") (pinfunction "1_1") (pintype "passive"))
      (node (ref "D1") (pin "+") (pinfunction "+_+") (pintype "passive"))
      (node (ref "LED2") (pin "+") (pinfunction "+_+") (pintype "passive"))
      (node (ref "U2") (pin "4") (pinfunction "VIN_4") (pintype "power_in"))
      (node (ref "U3") (pin "25") (pinfunction "VBUS_25") (pintype "bidirectional"))
      (node (ref "USB") (pin "VBUS") (pinfunction "VBUS_VBUS") (pintype "bidirectional"))
    )
    (net (code "61") (name "VCC") (class "Default")
      (node (ref "C102") (pin "2") (pinfunction "2_2") (pintype "passive"))
      (node (ref "C103") (pin "1") (pinfunction "1_1") (pintype "passive"))
      (node (ref "C17") (pin "+") (pinfunction "+_+") (pintype "passive"))
      (node (ref "C7") (pin "2") (pinfunction "2_2") (pintype "passive"))
      (node (ref "L1") (pin "1") (pinfunction "1_1") (pintype "passive"))
      (node (ref "L2") (pin "1") (pinfunction "1_1") (pintype "passive"))
      (node (ref "L3") (pin "1") (pinfunction "1_1") (pintype "passive"))
      (node (ref "U$13") (pin "1") (pinfunction "1_1") (pintype "passive"))
      (node (ref "U100") (pin "8") (pinfunction "VCC_8") (pintype "power_in"))
      (node (ref "VCC") (pin "2") (pinfunction "2_2") (pintype "passive"))
      (node (ref "Y101") (pin "1") (pinfunction "EN_1") (pintype "bidirectional"))
      (node (ref "Y101") (pin "4") (pinfunction "VCC_4") (pintype "bidirectional"))
    )
    (net (code "62") (name "VCCD") (class "Default")
      (node (ref "C13") (pin "1") (pinfunction "1_1") (pintype "passive"))
      (node (ref "U3") (pin "37") (pinfunction "VCCD_37") (pintype "bidirectional"))
    )
    (net (code "63") (name "VDDA") (class "Default")
      (node (ref "C8") (pin "1") (pinfunction "1_1") (pintype "passive"))
      (node (ref "C9") (pin "1") (pinfunction "1_1") (pintype "passive"))
      (node (ref "L1") (pin "2") (pinfunction "2_2") (pintype "passive"))
      (node (ref "U3") (pin "40") (pinfunction "VDDA_40") (pintype "bidirectional"))
    )
    (net (code "64") (name "VDDD") (class "Default")
      (node (ref "C10") (pin "1") (pinfunction "1_1") (pintype "passive"))
      (node (ref "C11") (pin "1") (pinfunction "1_1") (pintype "passive"))
      (node (ref "L2") (pin "2") (pinfunction "2_2") (pintype "passive"))
      (node (ref "U3") (pin "39") (pinfunction "VDDD_39") (pintype "bidirectional"))
    )
    (net (code "65") (name "VDDIO") (class "Default")
      (node (ref "C14") (pin "1") (pinfunction "1_1") (pintype "passive"))
      (node (ref "C15") (pin "1") (pinfunction "1_1") (pintype "passive"))
      (node (ref "L3") (pin "2") (pinfunction "2_2") (pintype "passive"))
      (node (ref "R10") (pin "2") (pinfunction "2_2") (pintype "passive"))
      (node (ref "R11") (pin "2") (pinfunction "2_2") (pintype "passive"))
      (node (ref "R9") (pin "2") (pinfunction "2_2") (pintype "passive"))
      (node (ref "U3") (pin "21") (pinfunction "VDDIO_21") (pintype "bidirectional"))
    )
    (net (code "66") (name "VIN") (class "Default")
      (node (ref "D1") (pin "-") (pinfunction "-_-") (pintype "passive"))
      (node (ref "D2") (pin "-") (pinfunction "-_-") (pintype "passive"))
      (node (ref "F1") (pin "1") (pinfunction "1_1") (pintype "bidirectional"))
    )
    (net (code "67") (name "unconnected-(BATTERY-PAD1-PadNC1)") (class "Default")
      (node (ref "BATTERY") (pin "NC1") (pinfunction "PAD1_NC1") (pintype "bidirectional"))
    )
    (net (code "68") (name "unconnected-(BATTERY-PAD2-PadNC2)") (class "Default")
      (node (ref "BATTERY") (pin "NC2") (pinfunction "PAD2_NC2") (pintype "bidirectional"))
    )
    (net (code "69") (name "unconnected-(J1-Pad1)") (class "Default")
      (node (ref "J1") (pin "1") (pinfunction "1_1") (pintype "passive"))
    )
    (net (code "70") (name "unconnected-(J1-Pad2)") (class "Default")
      (node (ref "J1") (pin "2") (pinfunction "2_2") (pintype "passive"))
    )
    (net (code "71") (name "unconnected-(J1-Pad3)") (class "Default")
      (node (ref "J1") (pin "3") (pinfunction "3_3") (pintype "passive"))
    )
    (net (code "72") (name "unconnected-(J1-Pad4)") (class "Default")
      (node (ref "J1") (pin "4") (pinfunction "4_4") (pintype "passive"))
    )
    (net (code "73") (name "unconnected-(J1-Pad5)") (class "Default")
      (node (ref "J1") (pin "5") (pinfunction "5_5") (pintype "passive"))
    )
    (net (code "74") (name "unconnected-(J1-Pad6)") (class "Default")
      (node (ref "J1") (pin "6") (pinfunction "6_6") (pintype "passive"))
    )
    (net (code "75") (name "unconnected-(J1-Pad7)") (class "Default")
      (node (ref "J1") (pin "7") (pinfunction "7_7") (pintype "passive"))
    )
    (net (code "76") (name "unconnected-(J1-Pad8)") (class "Default")
      (node (ref "J1") (pin "8") (pinfunction "8_8") (pintype "passive"))
    )
    (net (code "77") (name "unconnected-(J1-Pad9)") (class "Default")
      (node (ref "J1") (pin "9") (pinfunction "9_9") (pintype "passive"))
    )
    (net (code "78") (name "unconnected-(J1-Pad10)") (class "Default")
      (node (ref "J1") (pin "10") (pinfunction "10_10") (pintype "passive"))
    )
    (net (code "79") (name "unconnected-(J1-Pad11)") (class "Default")
      (node (ref "J1") (pin "11") (pinfunction "11_11") (pintype "passive"))
    )
    (net (code "80") (name "unconnected-(J1-Pad12)") (class "Default")
      (node (ref "J1") (pin "12") (pinfunction "12_12") (pintype "passive"))
    )
    (net (code "81") (name "unconnected-(J1-Pad13)") (class "Default")
      (node (ref "J1") (pin "13") (pinfunction "13_13") (pintype "passive"))
    )
    (net (code "82") (name "unconnected-(J1-Pad14)") (class "Default")
      (node (ref "J1") (pin "14") (pinfunction "14_14") (pintype "passive"))
    )
    (net (code "83") (name "unconnected-(J1-Pad15)") (class "Default")
      (node (ref "J1") (pin "15") (pinfunction "15_15") (pintype "passive"))
    )
    (net (code "84") (name "unconnected-(J1-Pad16)") (class "Default")
      (node (ref "J1") (pin "16") (pinfunction "16_16") (pintype "passive"))
    )
    (net (code "85") (name "unconnected-(JP1-PadD+)") (class "Default")
      (node (ref "JP1") (pin "D+") (pinfunction "D+_D+") (pintype "bidirectional"))
    )
    (net (code "86") (name "unconnected-(JP1-PadD-)") (class "Default")
      (node (ref "JP1") (pin "D-") (pinfunction "D-_D-") (pintype "bidirectional"))
    )
    (net (code "87") (name "unconnected-(JP1-PadGND)") (class "Default")
      (node (ref "JP1") (pin "GND") (pinfunction "GND_GND") (pintype "bidirectional"))
    )
    (net (code "88") (name "unconnected-(JP1-PadVBUS)") (class "Default")
      (node (ref "JP1") (pin "VBUS") (pinfunction "VBUS_VBUS") (pintype "bidirectional"))
    )
    (net (code "89") (name "unconnected-(JP2-Pad2)") (class "Default")
      (node (ref "JP2") (pin "2") (pinfunction "2_2") (pintype "passive"))
    )
    (net (code "90") (name "unconnected-(JP2-Pad4)") (class "Default")
      (node (ref "JP2") (pin "4") (pinfunction "4_4") (pintype "passive"))
    )
    (net (code "91") (name "unconnected-(JP2-Pad6)") (class "Default")
      (node (ref "JP2") (pin "6") (pinfunction "6_6") (pintype "passive"))
    )
    (net (code "92") (name "unconnected-(JP2-Pad8)") (class "Default")
      (node (ref "JP2") (pin "8") (pinfunction "8_8") (pintype "passive"))
    )
    (net (code "93") (name "unconnected-(JP2-Pad10)") (class "Default")
      (node (ref "JP2") (pin "10") (pinfunction "10_10") (pintype "passive"))
    )
    (net (code "94") (name "unconnected-(JP2-Pad12)") (class "Default")
      (node (ref "JP2") (pin "12") (pinfunction "12_12") (pintype "passive"))
    )
    (net (code "95") (name "unconnected-(MIDI_IN-Pad1)") (class "Default")
      (node (ref "MIDI_IN") (pin "1") (pinfunction "1_1") (pintype "bidirectional"))
    )
    (net (code "96") (name "unconnected-(MIDI_IN-Pad2)") (class "Default")
      (node (ref "MIDI_IN") (pin "2") (pinfunction "2_2") (pintype "bidirectional"))
    )
    (net (code "97") (name "unconnected-(MIDI_IN-Pad3)") (class "Default")
      (node (ref "MIDI_IN") (pin "3") (pinfunction "3_3") (pintype "bidirectional"))
    )
    (net (code "98") (name "unconnected-(MIDI_OUT-Pad1)") (class "Default")
      (node (ref "MIDI_OUT") (pin "1") (pinfunction "1_1") (pintype "bidirectional"))
    )
    (net (code "99") (name "unconnected-(MIDI_OUT-Pad3)") (class "Default")
      (node (ref "MIDI_OUT") (pin "3") (pinfunction "3_3") (pintype "bidirectional"))
    )
    (net (code "100") (name "unconnected-(OK1-VE-Pad7)") (class "Default")
      (node (ref "OK1") (pin "7") (pinfunction "VE_7") (pintype "passive"))
    )
    (net (code "101") (name "unconnected-(U3-NC-Pad11)") (class "Default")
      (node (ref "U3") (pin "11") (pinfunction "NC_11") (pintype "bidirectional"))
    )
    (net (code "102") (name "unconnected-(U3-NC-Pad15)") (class "Default")
      (node (ref "U3") (pin "15") (pinfunction "NC_15") (pintype "bidirectional"))
    )
  )
)
